# untitled.net
KiCad netlist of a schematic drawn in EAGLE
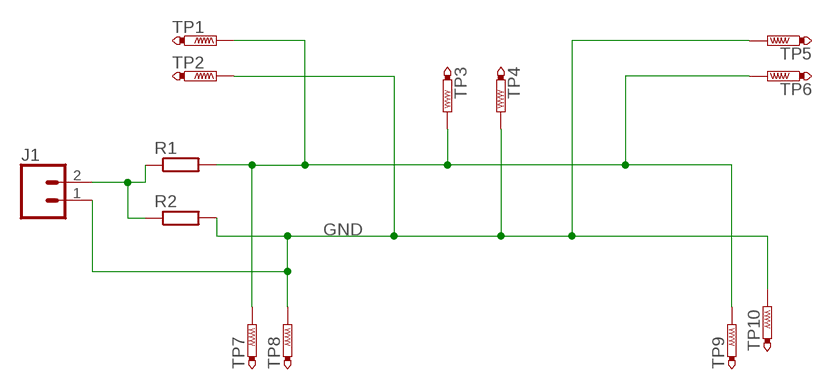
[diagram p0: schematic, sheet 1]

(export (version "E")
  (design (tool "Eeschema 10.0.6"))
  (components
    (comp (ref "J1")
      (value "CONN_02LOCK_LONGPADS")
      (footprint "eagle-import:1X02_LOCK_LONGPADS")
      (libsource (lib "eagle-import") (part "CONN_02LOCK_LONGPADS"))
    )
    (comp (ref "R1")
      (value "R-EU_0207/12")
      (footprint "eagle-import:0207_12")
      (libsource (lib "eagle-import") (part "R-EU_0207/12"))
    )
    (comp (ref "R2")
      (value "R-EU_0207/12")
      (footprint "eagle-import:0207_12")
      (libsource (lib "eagle-import") (part "R-EU_0207/12"))
    )
    (comp (ref "TP1")
      (value "PTR1TP20R")
      (footprint "eagle-import:TP20R")
      (libsource (lib "eagle-import") (part "PTR1TP20R"))
    )
    (comp (ref "TP2")
      (value "PTR1TP20R")
      (footprint "eagle-import:TP20R")
      (libsource (lib "eagle-import") (part "PTR1TP20R"))
    )
    (comp (ref "TP3")
      (value "PTR1TP20R")
      (footprint "eagle-import:TP20R")
      (libsource (lib "eagle-import") (part "PTR1TP20R"))
    )
    (comp (ref "TP4")
      (value "PTR1TP20R")
      (footprint "eagle-import:TP20R")
      (libsource (lib "eagle-import") (part "PTR1TP20R"))
    )
    (comp (ref "TP5")
      (value "PTR1TP20R")
      (footprint "eagle-import:TP20R")
      (libsource (lib "eagle-import") (part "PTR1TP20R"))
    )
    (comp (ref "TP6")
      (value "PTR1TP20R")
      (footprint "eagle-import:TP20R")
      (libsource (lib "eagle-import") (part "PTR1TP20R"))
    )
    (comp (ref "TP7")
      (value "PTR1TP20R")
      (footprint "eagle-import:TP20R")
      (libsource (lib "eagle-import") (part "PTR1TP20R"))
    )
    (comp (ref "TP8")
      (value "PTR1TP20R")
      (footprint "eagle-import:TP20R")
      (libsource (lib "eagle-import") (part "PTR1TP20R"))
    )
    (comp (ref "TP9")
      (value "PTR1TP20R")
      (footprint "eagle-import:TP20R")
      (libsource (lib "eagle-import") (part "PTR1TP20R"))
    )
    (comp (ref "TP10")
      (value "PTR1TP20R")
      (footprint "eagle-import:TP20R")
      (libsource (lib "eagle-import") (part "PTR1TP20R"))
    )
  )
  (nets
    (net (code "1") (name "/GND") (class "Default")
      (node (ref "J1") (pin "1") (pinfunction "1_1") (pintype "passive"))
      (node (ref "R2") (pin "2") (pinfunction "2_2") (pintype "passive"))
      (node (ref "TP10") (pin "TP") (pinfunction "TP_TP") (pintype "input"))
      (node (ref "TP2") (pin "TP") (pinfunction "TP_TP") (pintype "input"))
      (node (ref "TP4") (pin "TP") (pinfunction "TP_TP") (pintype "input"))
      (node (ref "TP5") (pin "TP") (pinfunction "TP_TP") (pintype "input"))
      (node (ref "TP8") (pin "TP") (pinfunction "TP_TP") (pintype "input"))
    )
    (net (code "2") (name "Net-(J1-Pad2)") (class "Default")
      (node (ref "J1") (pin "2") (pinfunction "2_2") (pintype "passive"))
      (node (ref "R1") (pin "1") (pinfunction "1_1") (pintype "passive"))
      (node (ref "R2") (pin "1") (pinfunction "1_1") (pintype "passive"))
    )
    (net (code "3") (name "Net-(R1-Pad2)") (class "Default")
      (node (ref "R1") (pin "2") (pinfunction "2_2") (pintype "passive"))
      (node (ref "TP1") (pin "TP") (pinfunction "TP_TP") (pintype "input"))
      (node (ref "TP3") (pin "TP") (pinfunction "TP_TP") (pintype "input"))
      (node (ref "TP6") (pin "TP") (pinfunction "TP_TP") (pintype "input"))
      (node (ref "TP7") (pin "TP") (pinfunction "TP_TP") (pintype "input"))
      (node (ref "TP9") (pin "TP") (pinfunction "TP_TP") (pintype "input"))
    )
  )
)
